# PLD_Thermometers_PT1000.net
KiCad netlist of a schematic drawn in Altium Designer
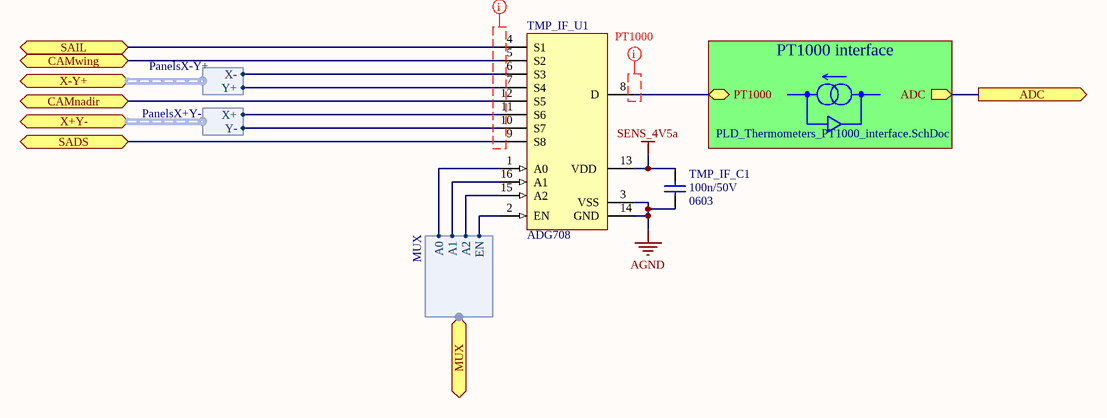
[diagram p0: PLD_Thermometers_PT1000.SchDoc]

(export (version "E")
  (design (tool "Eeschema 10.0.6"))
  (components
    (comp (ref "TMP_IF_C1")
      (value "100n/50V")
      (footprint "SMD_Capacitor_0603")
      (description "Ceramic Cap Kemet COTS 100n/50V X7R 0603")
      (fields
        (field (name "MANUFACTURER") "Kemet")
        (field (name "MANUFACTURERPARTNUMBER") "C0603T104K5RALTU")
        (field (name "PACKAGE") "0603")
      )
      (libsource (lib "capacitors") (part "Cer_C0603T104K5RALTU"))
    )
    (comp (ref "TMP_IF_U1")
      (value "ADG708")
      (footprint "TSSOP16")
      (description "CMOS Analog 8:1 Multiplexer")
      (fields (field (name "MANUFACTURER") "Analog Devices") (field (name "MANUFACTURERPARTNUMBER") "ADG708"))
      (libsource (lib "microcircuits") (part "ADG708"))
    )
  )
  (nets
    (net (code "4") (name "/A0") (class "Default")
      (node (ref "TMP_IF_U1") (pin "1") (pinfunction "A0_1") (pintype "input"))
    )
    (net (code "5") (name "/A1") (class "Default")
      (node (ref "TMP_IF_U1") (pin "16") (pinfunction "A1_16") (pintype "input"))
    )
    (net (code "6") (name "/A2") (class "Default")
      (node (ref "TMP_IF_U1") (pin "15") (pinfunction "A2_15") (pintype "input"))
    )
    (net (code "8") (name "/CAMnadir") (class "Default")
      (node (ref "TMP_IF_U1") (pin "12") (pinfunction "S5_12") (pintype "passive"))
    )
    (net (code "9") (name "/CAMwing") (class "Default")
      (node (ref "TMP_IF_U1") (pin "5") (pinfunction "S2_5") (pintype "passive"))
    )
    (net (code "10") (name "/EN") (class "Default")
      (node (ref "TMP_IF_U1") (pin "2") (pinfunction "EN_2") (pintype "input"))
    )
    (net (code "11") (name "/PT1000") (class "Default")
      (node (ref "TMP_IF_U1") (pin "8") (pinfunction "D_8") (pintype "passive"))
    )
    (net (code "12") (name "/SADS") (class "Default")
      (node (ref "TMP_IF_U1") (pin "9") (pinfunction "S8_9") (pintype "passive"))
    )
    (net (code "13") (name "/SAIL") (class "Default")
      (node (ref "TMP_IF_U1") (pin "4") (pinfunction "S1_4") (pintype "passive"))
    )
    (net (code "14") (name "/X+") (class "Default")
      (node (ref "TMP_IF_U1") (pin "11") (pinfunction "S6_11") (pintype "passive"))
    )
    (net (code "15") (name "/X-") (class "Default")
      (node (ref "TMP_IF_U1") (pin "6") (pinfunction "S3_6") (pintype "passive"))
    )
    (net (code "16") (name "/Y+") (class "Default")
      (node (ref "TMP_IF_U1") (pin "7") (pinfunction "S4_7") (pintype "passive"))
    )
    (net (code "17") (name "/Y-") (class "Default")
      (node (ref "TMP_IF_U1") (pin "10") (pinfunction "S7_10") (pintype "passive"))
    )
    (net (code "21") (name "AGND") (class "Default")
      (node (ref "TMP_IF_C1") (pin "2") (pinfunction "2_2") (pintype "passive"))
      (node (ref "TMP_IF_U1") (pin "14") (pinfunction "GND_14") (pintype "power_in"))
      (node (ref "TMP_IF_U1") (pin "3") (pinfunction "VSS_3") (pintype "power_in"))
    )
    (net (code "22") (name "SENS_4V5a") (class "Default")
      (node (ref "TMP_IF_C1") (pin "1") (pinfunction "1_1") (pintype "passive"))
      (node (ref "TMP_IF_U1") (pin "13") (pinfunction "VDD_13") (pintype "power_in"))
    )
  )
)
